# Franzininho.net
KiCad netlist of a schematic drawn in EAGLE
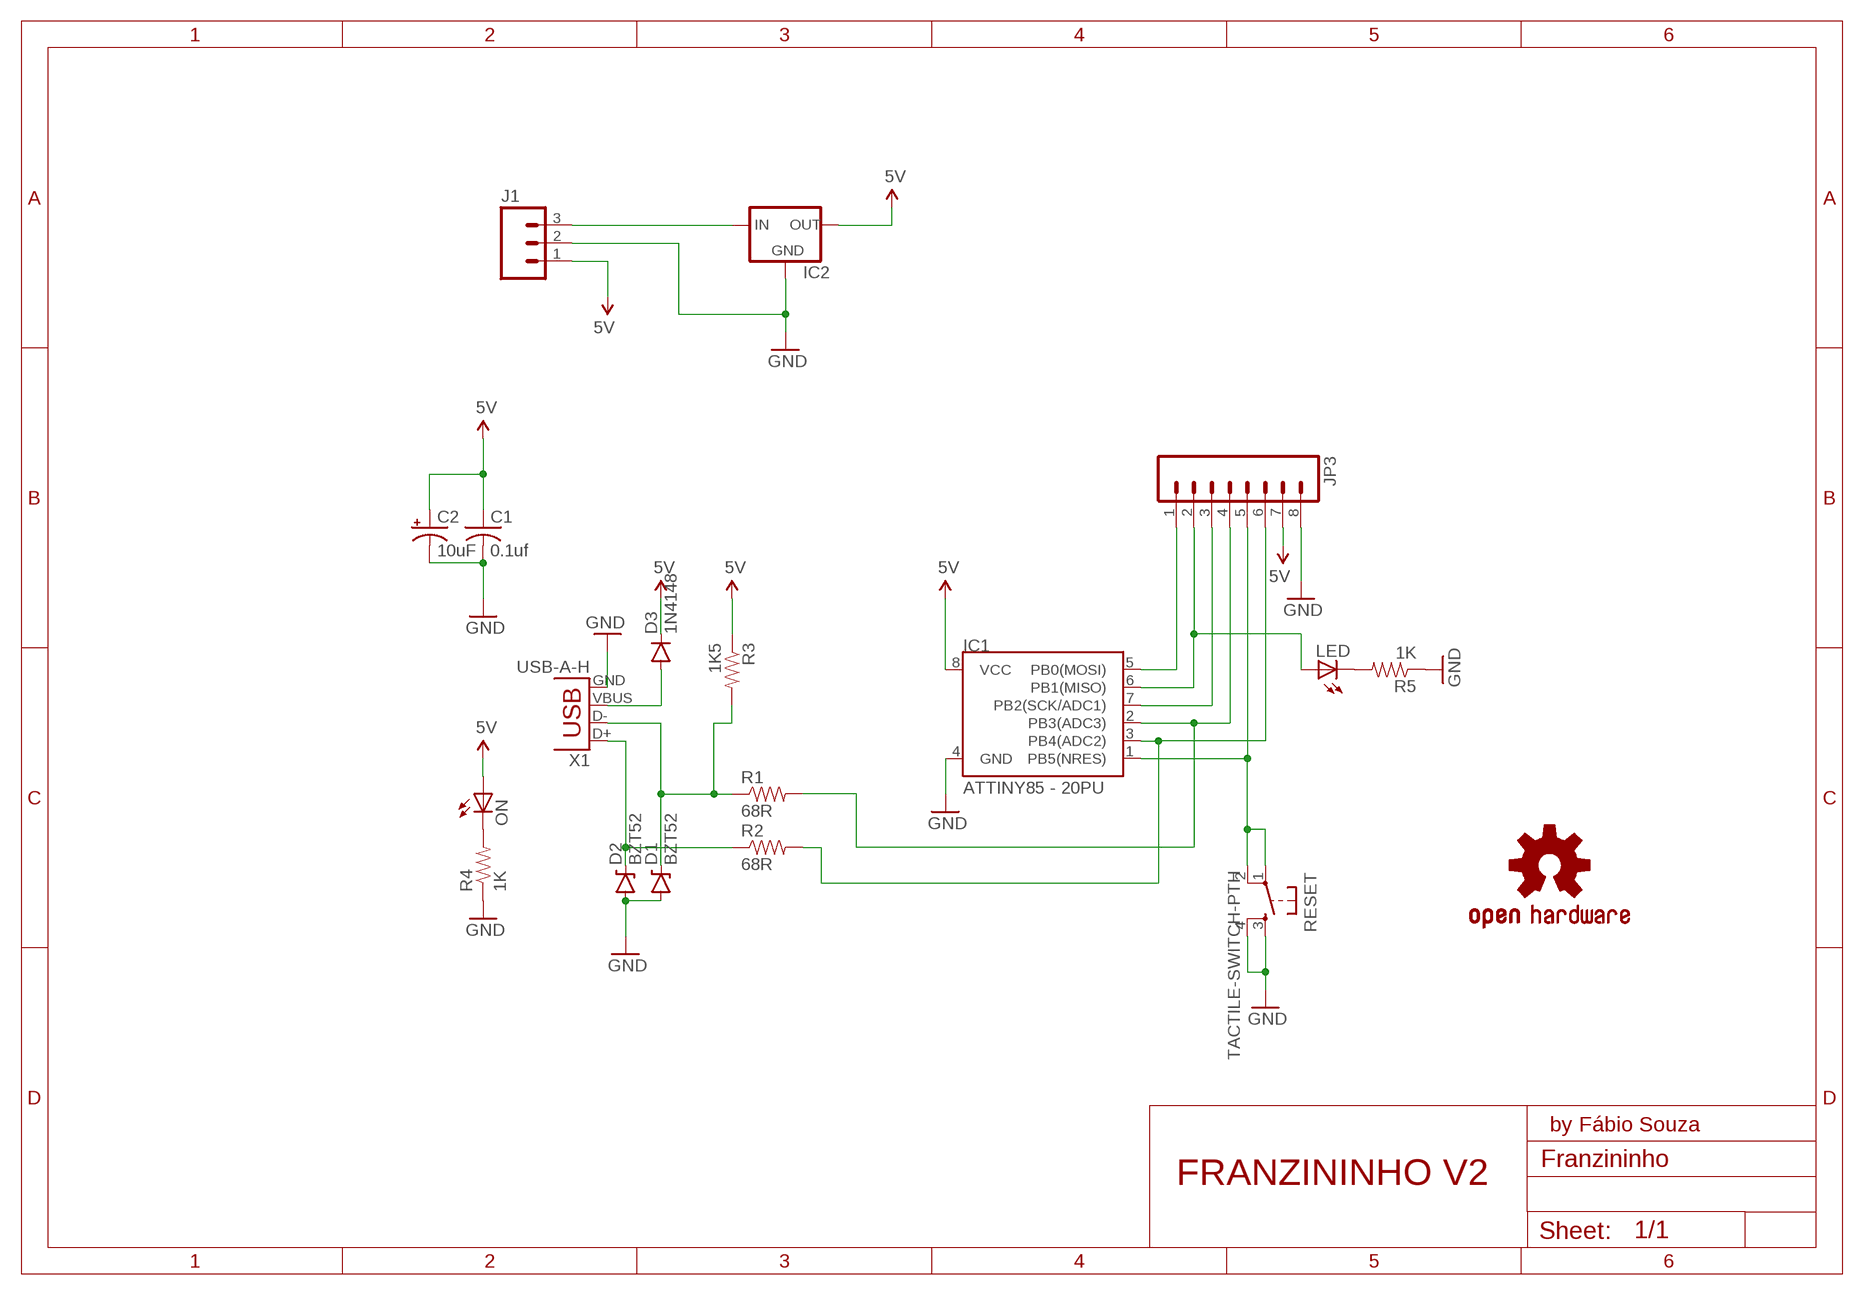
[diagram p0: schematic, sheet 1]

(export (version "E")
  (design (tool "Eeschema 10.0.6"))
  (components
    (comp (ref "C1")
      (value "0.1uf")
      (footprint "eagle-import:C025-025X050")
      (libsource (lib "eagle-import") (part "C-US025-025X050"))
    )
    (comp (ref "C2")
      (value "10uF")
      (footprint "eagle-import:E2,5-6E")
      (libsource (lib "eagle-import") (part "CPOL-USE2,5-6E"))
    )
    (comp (ref "D1")
      (value "BZT52")
      (footprint "eagle-import:DIODE-BZT52")
      (libsource (lib "eagle-import") (part "DIODE-ZENER"))
    )
    (comp (ref "D2")
      (value "BZT52")
      (footprint "eagle-import:DIODE-BZT52")
      (libsource (lib "eagle-import") (part "DIODE-ZENER"))
    )
    (comp (ref "D3")
      (value "1N4148")
      (footprint "eagle-import:DIODE-1N4148")
      (libsource (lib "eagle-import") (part "DIODE1N4148"))
    )
    (comp (ref "IC1")
      (value "ATTINY85 - 20PU")
      (footprint "eagle-import:DIP08")
      (libsource (lib "eagle-import") (part "ATTINY45TINY45-20-DIP"))
    )
    (comp (ref "IC2")
      (value "78LXX")
      (footprint "eagle-import:78LXX")
      (libsource (lib "eagle-import") (part "78LXX"))
    )
    (comp (ref "J1")
      (value "M03PTH")
      (footprint "eagle-import:1X03")
      (libsource (lib "eagle-import") (part "M03PTH"))
    )
    (comp (ref "JP3")
      (value "M08")
      (footprint "eagle-import:1X08_ROUND")
      (libsource (lib "eagle-import") (part "M08"))
    )
    (comp (ref "LED")
      (value "LED3MM")
      (footprint "eagle-import:LED3MM")
      (libsource (lib "eagle-import") (part "LED3MM"))
    )
    (comp (ref "LOGO1")
      (value "OSHW-LOGOM")
      (footprint "eagle-import:OSHW-LOGO-M")
      (libsource (lib "eagle-import") (part "OSHW-LOGOM"))
    )
    (comp (ref "ON")
      (value "LED3MM")
      (footprint "eagle-import:LED3MM")
      (libsource (lib "eagle-import") (part "LED3MM"))
    )
    (comp (ref "R1")
      (value "68R")
      (footprint "eagle-import:AXIAL-0.4")
      (libsource (lib "eagle-import") (part "RESISTORPTH-1/4W"))
    )
    (comp (ref "R2")
      (value "68R")
      (footprint "eagle-import:AXIAL-0.4")
      (libsource (lib "eagle-import") (part "RESISTORPTH-1/4W"))
    )
    (comp (ref "R3")
      (value "1K5")
      (footprint "eagle-import:AXIAL-0.4")
      (libsource (lib "eagle-import") (part "RESISTORPTH-1/4W"))
    )
    (comp (ref "R4")
      (value "1K")
      (footprint "eagle-import:AXIAL-0.4")
      (libsource (lib "eagle-import") (part "RESISTORPTH-1/4W"))
    )
    (comp (ref "R5")
      (value "1K")
      (footprint "eagle-import:AXIAL-0.4")
      (libsource (lib "eagle-import") (part "RESISTORPTH-1/4W"))
    )
    (comp (ref "RESET")
      (value "TACTILE-SWITCH-PTH")
      (footprint "eagle-import:TAC-SWITCH-PTH")
      (libsource (lib "eagle-import") (part "TACTILE-SWITCH-PTH"))
    )
    (comp (ref "X1")
      (value "USB-A-H")
      (footprint "eagle-import:USB-A-H")
      (libsource (lib "eagle-import") (part "USB-A-H"))
    )
  )
  (nets
    (net (code "1") (name "5V") (class "Default")
      (node (ref "C1") (pin "1") (pinfunction "1_1") (pintype "passive"))
      (node (ref "C2") (pin "+") (pinfunction "+_+") (pintype "passive"))
      (node (ref "D3") (pin "C") (pinfunction "C_C") (pintype "passive"))
      (node (ref "IC1") (pin "8") (pinfunction "VCC_8") (pintype "bidirectional"))
      (node (ref "IC2") (pin "OUT") (pinfunction "OUT_OUT") (pintype "passive"))
      (node (ref "J1") (pin "1") (pinfunction "1_1") (pintype "passive"))
      (node (ref "JP3") (pin "7") (pinfunction "7_7") (pintype "passive"))
      (node (ref "ON") (pin "A") (pinfunction "A_A") (pintype "passive"))
      (node (ref "R3") (pin "P$1") (pinfunction "1_P$1") (pintype "passive"))
    )
    (net (code "2") (name "GND") (class "Default")
      (node (ref "C1") (pin "2") (pinfunction "2_2") (pintype "passive"))
      (node (ref "C2") (pin "-") (pinfunction "-_-") (pintype "passive"))
      (node (ref "D1") (pin "A") (pinfunction "A_A") (pintype "passive"))
      (node (ref "D2") (pin "A") (pinfunction "A_A") (pintype "passive"))
      (node (ref "IC1") (pin "4") (pinfunction "GND_4") (pintype "bidirectional"))
      (node (ref "IC2") (pin "GND") (pinfunction "GND_GND") (pintype "input"))
      (node (ref "J1") (pin "2") (pinfunction "2_2") (pintype "passive"))
      (node (ref "JP3") (pin "8") (pinfunction "8_8") (pintype "passive"))
      (node (ref "R4") (pin "P$1") (pinfunction "1_P$1") (pintype "passive"))
      (node (ref "R5") (pin "P$1") (pinfunction "1_P$1") (pintype "passive"))
      (node (ref "RESET") (pin "3") (pinfunction "3_3") (pintype "passive"))
      (node (ref "RESET") (pin "4") (pinfunction "4_4") (pintype "passive"))
      (node (ref "X1") (pin "GND") (pinfunction "GND_GND") (pintype "bidirectional"))
    )
    (net (code "3") (name "Net-(D3-PadA)") (class "Default")
      (node (ref "D3") (pin "A") (pinfunction "A_A") (pintype "passive"))
      (node (ref "X1") (pin "VBUS") (pinfunction "VBUS_VBUS") (pintype "bidirectional"))
    )
    (net (code "4") (name "Net-(IC1-PB0(MOSI))") (class "Default")
      (node (ref "IC1") (pin "5") (pinfunction "PB0(MOSI)_5") (pintype "bidirectional"))
      (node (ref "JP3") (pin "1") (pinfunction "1_1") (pintype "passive"))
    )
    (net (code "5") (name "Net-(IC1-PB1(MISO))") (class "Default")
      (node (ref "IC1") (pin "6") (pinfunction "PB1(MISO)_6") (pintype "bidirectional"))
      (node (ref "JP3") (pin "2") (pinfunction "2_2") (pintype "passive"))
      (node (ref "LED") (pin "A") (pinfunction "A_A") (pintype "passive"))
    )
    (net (code "6") (name "Net-(IC1-PB2(SCK{slash}ADC1))") (class "Default")
      (node (ref "IC1") (pin "7") (pinfunction "PB2(SCK/ADC1)_7") (pintype "bidirectional"))
      (node (ref "JP3") (pin "3") (pinfunction "3_3") (pintype "passive"))
    )
    (net (code "7") (name "Net-(IC1-PB3(ADC3))") (class "Default")
      (node (ref "IC1") (pin "2") (pinfunction "PB3(ADC3)_2") (pintype "bidirectional"))
      (node (ref "JP3") (pin "4") (pinfunction "4_4") (pintype "passive"))
      (node (ref "R1") (pin "P$2") (pinfunction "2_P$2") (pintype "passive"))
    )
    (net (code "8") (name "Net-(IC1-PB4(ADC2))") (class "Default")
      (node (ref "IC1") (pin "3") (pinfunction "PB4(ADC2)_3") (pintype "bidirectional"))
      (node (ref "JP3") (pin "6") (pinfunction "6_6") (pintype "passive"))
      (node (ref "R2") (pin "P$2") (pinfunction "2_P$2") (pintype "passive"))
    )
    (net (code "9") (name "Net-(IC1-PB5(NRES))") (class "Default")
      (node (ref "IC1") (pin "1") (pinfunction "PB5(NRES)_1") (pintype "bidirectional"))
      (node (ref "JP3") (pin "5") (pinfunction "5_5") (pintype "passive"))
      (node (ref "RESET") (pin "1") (pinfunction "1_1") (pintype "passive"))
      (node (ref "RESET") (pin "2") (pinfunction "2_2") (pintype "passive"))
    )
    (net (code "10") (name "Net-(IC2-PadIN)") (class "Default")
      (node (ref "IC2") (pin "IN") (pinfunction "IN_IN") (pintype "input"))
      (node (ref "J1") (pin "3") (pinfunction "3_3") (pintype "passive"))
    )
    (net (code "11") (name "Net-(LED-C)") (class "Default")
      (node (ref "LED") (pin "K") (pinfunction "C_K") (pintype "passive"))
      (node (ref "R5") (pin "P$2") (pinfunction "2_P$2") (pintype "passive"))
    )
    (net (code "12") (name "Net-(ON-C)") (class "Default")
      (node (ref "ON") (pin "K") (pinfunction "C_K") (pintype "passive"))
      (node (ref "R4") (pin "P$2") (pinfunction "2_P$2") (pintype "passive"))
    )
    (net (code "13") (name "Net-(R1-1)") (class "Default")
      (node (ref "D1") (pin "C") (pinfunction "C_C") (pintype "passive"))
      (node (ref "R1") (pin "P$1") (pinfunction "1_P$1") (pintype "passive"))
      (node (ref "R3") (pin "P$2") (pinfunction "2_P$2") (pintype "passive"))
      (node (ref "X1") (pin "D-") (pinfunction "D-_D-") (pintype "bidirectional"))
    )
    (net (code "14") (name "Net-(R2-1)") (class "Default")
      (node (ref "D2") (pin "C") (pinfunction "C_C") (pintype "passive"))
      (node (ref "R2") (pin "P$1") (pinfunction "1_P$1") (pintype "passive"))
      (node (ref "X1") (pin "D+") (pinfunction "D+_D+") (pintype "bidirectional"))
    )
  )
)
